# DRV10987.net
KiCad netlist of a schematic drawn in EAGLE
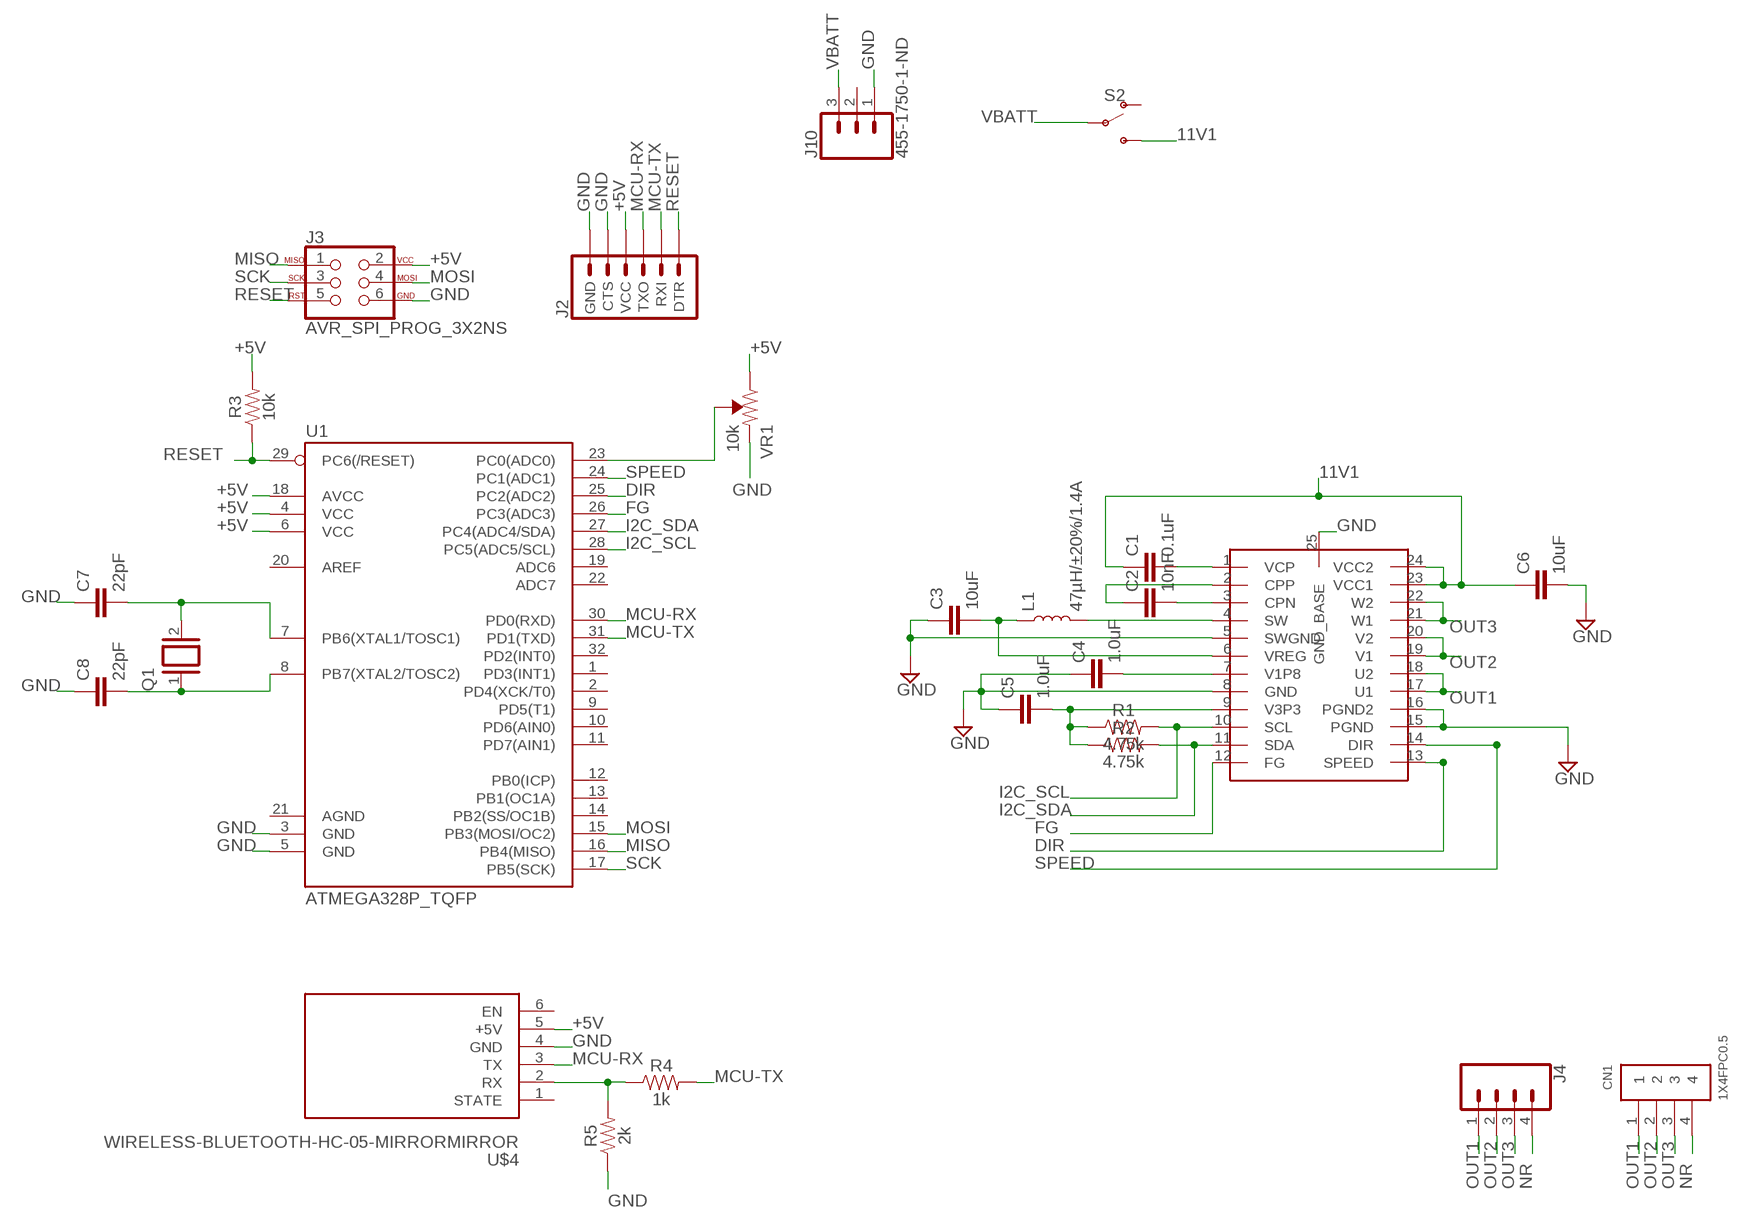
[diagram p0: schematic, sheet 1]

(export (version "E")
  (design (tool "Eeschema 10.0.6"))
  (components
    (comp (ref "C1")
      (value "0.1uF")
      (footprint "eagle-import:0805")
      (libsource (lib "eagle-import") (part "1.0UF-0805-25V-10%"))
    )
    (comp (ref "C2")
      (value "10nF")
      (footprint "eagle-import:0805")
      (libsource (lib "eagle-import") (part "1.0UF-0805-25V-10%"))
    )
    (comp (ref "C3")
      (value "10uF")
      (footprint "eagle-import:0805")
      (libsource (lib "eagle-import") (part "1.0UF-0805-25V-10%"))
    )
    (comp (ref "C4")
      (value "1.0uF")
      (footprint "eagle-import:0805")
      (libsource (lib "eagle-import") (part "1.0UF-0805-25V-10%"))
    )
    (comp (ref "C5")
      (value "1.0uF")
      (footprint "eagle-import:0805")
      (libsource (lib "eagle-import") (part "1.0UF-0805-25V-10%"))
    )
    (comp (ref "C6")
      (value "10uF")
      (footprint "eagle-import:0805")
      (libsource (lib "eagle-import") (part "1.0UF-0805-25V-10%"))
    )
    (comp (ref "C7")
      (value "22pF")
      (footprint "eagle-import:1206")
      (libsource (lib "eagle-import") (part "2.2UF-1206-50V-10%"))
    )
    (comp (ref "C8")
      (value "22pF")
      (footprint "eagle-import:1206")
      (libsource (lib "eagle-import") (part "2.2UF-1206-50V-10%"))
    )
    (comp (ref "CN1")
      (value "1X4FPC0.5")
      (footprint "eagle-import:FPC_0.5MM-4")
      (libsource (lib "eagle-import") (part "1X4FPC0.5"))
    )
    (comp (ref "J2")
      (value "6_PIN_SERIAL_TARGET")
      (footprint "eagle-import:1X06")
      (libsource (lib "eagle-import") (part "6_PIN_SERIAL_TARGET"))
    )
    (comp (ref "J3")
      (value "AVR_SPI_PROG_3X2NS")
      (footprint "eagle-import:2X3-NS")
      (libsource (lib "eagle-import") (part "AVR_SPI_PROG_3X2NS"))
    )
    (comp (ref "J4")
      (value "CONN_04")
      (footprint "eagle-import:1X04")
      (libsource (lib "eagle-import") (part "CONN_04"))
    )
    (comp (ref "J10")
      (value "455-1750-1-ND")
      (footprint "eagle-import:1X03")
      (libsource (lib "eagle-import") (part "CONN_03"))
    )
    (comp (ref "L1")
      (value "47µH/±20%/1.4A")
      (footprint "eagle-import:SRN6045")
      (libsource (lib "eagle-import") (part "INDUCTOR-SRN6045-33UH"))
    )
    (comp (ref "Q1")
      (value "XTAL/S")
      (footprint "eagle-import:QS")
      (libsource (lib "eagle-import") (part "XTAL/S"))
    )
    (comp (ref "R1")
      (value "4.75k")
      (footprint "eagle-import:0805")
      (libsource (lib "eagle-import") (part "RESISTOR0805"))
    )
    (comp (ref "R2")
      (value "4.75k")
      (footprint "eagle-import:0805")
      (libsource (lib "eagle-import") (part "RESISTOR0805"))
    )
    (comp (ref "R3")
      (value "10k")
      (footprint "eagle-import:1206")
      (libsource (lib "eagle-import") (part "RESISTOR1206"))
    )
    (comp (ref "R4")
      (value "1k")
      (footprint "eagle-import:AXIAL-0.3")
      (libsource (lib "eagle-import") (part "1KOHM-HORIZ-1/4W-5%"))
    )
    (comp (ref "R5")
      (value "2k")
      (footprint "eagle-import:AXIAL-0.3")
      (libsource (lib "eagle-import") (part "resistors-longpads_RESISTORAXIAL-0.3"))
    )
    (comp (ref "S2")
      (value "SWITCH-SPDT-PTH-11.6X4.0MM")
      (footprint "eagle-import:SWITCH_SPDT_PTH_11.6X4.0MM")
      (libsource (lib "eagle-import") (part "SWITCH-SPDT-PTH-11.6X4.0MM"))
    )
    (comp (ref "U$1")
      (value "DRV10987")
      (footprint "eagle-import:DRV10987")
      (libsource (lib "eagle-import") (part "DRV10987"))
    )
    (comp (ref "U$4")
      (value "WIRELESS-BLUETOOTH-HC-05-MIRRORMIRROR")
      (footprint "eagle-import:WIRELESS-BLUETOOTH-HC-05-MIRROR")
      (libsource (lib "eagle-import") (part "WIRELESS-BLUETOOTH-HC-05-MIRRORMIRROR"))
    )
    (comp (ref "U1")
      (value "ATMEGA328P_TQFP")
      (footprint "eagle-import:TQFP32-08")
      (libsource (lib "eagle-import") (part "ATMEGA328P_TQFP"))
    )
    (comp (ref "VR1")
      (value "10k")
      (footprint "eagle-import:TRIMPOT-PTH-3386U")
      (libsource (lib "eagle-import") (part "TRIMPOT-PTH-10MM-KNOB-1/2W-10%"))
    )
  )
  (nets
    (net (code "1") (name "/+5V") (class "Default")
      (node (ref "J2") (pin "4") (pinfunction "VCC_4") (pintype "passive"))
      (node (ref "J3") (pin "2") (pinfunction "2_2") (pintype "passive"))
      (node (ref "R3") (pin "2") (pinfunction "2_2") (pintype "passive"))
      (node (ref "U$4") (pin "5") (pinfunction "+5V_5") (pintype "power_in"))
      (node (ref "U1") (pin "18") (pinfunction "AVCC_18") (pintype "bidirectional"))
      (node (ref "U1") (pin "4") (pinfunction "VCC_4") (pintype "bidirectional"))
      (node (ref "U1") (pin "6") (pinfunction "VCC_6") (pintype "bidirectional"))
      (node (ref "VR1") (pin "3") (pinfunction "CW_3") (pintype "passive"))
    )
    (net (code "2") (name "/11V1") (class "Default")
      (node (ref "C1") (pin "1") (pinfunction "1_1") (pintype "passive"))
      (node (ref "C6") (pin "1") (pinfunction "1_1") (pintype "passive"))
      (node (ref "S2") (pin "3") (pinfunction "S_3") (pintype "passive"))
      (node (ref "U$1") (pin "23") (pinfunction "VCC1_23") (pintype "bidirectional"))
      (node (ref "U$1") (pin "24") (pinfunction "VCC2_24") (pintype "bidirectional"))
    )
    (net (code "3") (name "/DIR") (class "Default")
      (node (ref "U$1") (pin "13") (pinfunction "SPEED_13") (pintype "bidirectional"))
      (node (ref "U1") (pin "25") (pinfunction "PC2(ADC2)_25") (pintype "bidirectional"))
    )
    (net (code "4") (name "/FG") (class "Default")
      (node (ref "U$1") (pin "12") (pinfunction "FG_12") (pintype "bidirectional"))
      (node (ref "U1") (pin "26") (pinfunction "PC3(ADC3)_26") (pintype "bidirectional"))
    )
    (net (code "5") (name "/I2C_SCL") (class "Default")
      (node (ref "R1") (pin "2") (pinfunction "2_2") (pintype "passive"))
      (node (ref "U$1") (pin "10") (pinfunction "SCL_10") (pintype "bidirectional"))
      (node (ref "U1") (pin "28") (pinfunction "PC5(ADC5/SCL)_28") (pintype "bidirectional"))
    )
    (net (code "6") (name "/I2C_SDA") (class "Default")
      (node (ref "R2") (pin "2") (pinfunction "2_2") (pintype "passive"))
      (node (ref "U$1") (pin "11") (pinfunction "SDA_11") (pintype "bidirectional"))
      (node (ref "U1") (pin "27") (pinfunction "PC4(ADC4/SDA)_27") (pintype "bidirectional"))
    )
    (net (code "7") (name "/MCU-RX") (class "Default")
      (node (ref "J2") (pin "3") (pinfunction "TXO_3") (pintype "passive"))
      (node (ref "U$4") (pin "3") (pinfunction "TX_3") (pintype "bidirectional"))
      (node (ref "U1") (pin "30") (pinfunction "PD0(RXD)_30") (pintype "bidirectional"))
    )
    (net (code "8") (name "/MCU-TX") (class "Default")
      (node (ref "J2") (pin "2") (pinfunction "RXI_2") (pintype "passive"))
      (node (ref "R4") (pin "P$2") (pinfunction "2_P$2") (pintype "passive"))
      (node (ref "U1") (pin "31") (pinfunction "PD1(TXD)_31") (pintype "bidirectional"))
    )
    (net (code "9") (name "/MISO") (class "Default")
      (node (ref "J3") (pin "1") (pinfunction "1_1") (pintype "passive"))
      (node (ref "U1") (pin "16") (pinfunction "PB4(MISO)_16") (pintype "bidirectional"))
    )
    (net (code "10") (name "/MOSI") (class "Default")
      (node (ref "J3") (pin "4") (pinfunction "4_4") (pintype "passive"))
      (node (ref "U1") (pin "15") (pinfunction "PB3(MOSI/OC2)_15") (pintype "bidirectional"))
    )
    (net (code "11") (name "/NR") (class "Default")
      (node (ref "CN1") (pin "4") (pinfunction "4_4") (pintype "bidirectional"))
      (node (ref "J4") (pin "4") (pinfunction "4_4") (pintype "passive"))
    )
    (net (code "12") (name "/OUT1") (class "Default")
      (node (ref "CN1") (pin "1") (pinfunction "1_1") (pintype "bidirectional"))
      (node (ref "J4") (pin "1") (pinfunction "1_1") (pintype "passive"))
      (node (ref "U$1") (pin "17") (pinfunction "U1_17") (pintype "bidirectional"))
      (node (ref "U$1") (pin "18") (pinfunction "U2_18") (pintype "bidirectional"))
    )
    (net (code "13") (name "/OUT2") (class "Default")
      (node (ref "CN1") (pin "2") (pinfunction "2_2") (pintype "bidirectional"))
      (node (ref "J4") (pin "2") (pinfunction "2_2") (pintype "passive"))
      (node (ref "U$1") (pin "19") (pinfunction "V1_19") (pintype "bidirectional"))
      (node (ref "U$1") (pin "20") (pinfunction "V2_20") (pintype "bidirectional"))
    )
    (net (code "14") (name "/OUT3") (class "Default")
      (node (ref "CN1") (pin "3") (pinfunction "3_3") (pintype "bidirectional"))
      (node (ref "J4") (pin "3") (pinfunction "3_3") (pintype "passive"))
      (node (ref "U$1") (pin "21") (pinfunction "W1_21") (pintype "bidirectional"))
      (node (ref "U$1") (pin "22") (pinfunction "W2_22") (pintype "bidirectional"))
    )
    (net (code "15") (name "/RESET") (class "Default")
      (node (ref "J2") (pin "1") (pinfunction "DTR_1") (pintype "passive"))
      (node (ref "J3") (pin "5") (pinfunction "5_5") (pintype "passive"))
      (node (ref "R3") (pin "1") (pinfunction "1_1") (pintype "passive"))
      (node (ref "U1") (pin "29") (pinfunction "PC6(/RESET)_29") (pintype "bidirectional"))
    )
    (net (code "16") (name "/SCK") (class "Default")
      (node (ref "J3") (pin "3") (pinfunction "3_3") (pintype "passive"))
      (node (ref "U1") (pin "17") (pinfunction "PB5(SCK)_17") (pintype "bidirectional"))
    )
    (net (code "17") (name "/SPEED") (class "Default")
      (node (ref "U$1") (pin "14") (pinfunction "DIR_14") (pintype "bidirectional"))
      (node (ref "U1") (pin "24") (pinfunction "PC1(ADC1)_24") (pintype "bidirectional"))
    )
    (net (code "18") (name "/VBATT") (class "Default")
      (node (ref "J10") (pin "3") (pinfunction "3_3") (pintype "passive"))
      (node (ref "S2") (pin "2") (pinfunction "P_2") (pintype "passive"))
    )
    (net (code "19") (name "GND") (class "Default")
      (node (ref "C3") (pin "1") (pinfunction "1_1") (pintype "passive"))
      (node (ref "C4") (pin "1") (pinfunction "1_1") (pintype "passive"))
      (node (ref "C5") (pin "1") (pinfunction "1_1") (pintype "passive"))
      (node (ref "C6") (pin "2") (pinfunction "2_2") (pintype "passive"))
      (node (ref "C7") (pin "1") (pinfunction "1_1") (pintype "passive"))
      (node (ref "C8") (pin "1") (pinfunction "1_1") (pintype "passive"))
      (node (ref "J10") (pin "1") (pinfunction "1_1") (pintype "passive"))
      (node (ref "J2") (pin "5") (pinfunction "CTS_5") (pintype "passive"))
      (node (ref "J2") (pin "6") (pinfunction "GND_6") (pintype "passive"))
      (node (ref "J3") (pin "6") (pinfunction "6_6") (pintype "passive"))
      (node (ref "R5") (pin "P$1") (pinfunction "1_P$1") (pintype "passive"))
      (node (ref "U$1") (pin "15") (pinfunction "PGND_15") (pintype "bidirectional"))
      (node (ref "U$1") (pin "16") (pinfunction "PGND2_16") (pintype "bidirectional"))
      (node (ref "U$1") (pin "25") (pinfunction "GND_BASE_25") (pintype "bidirectional"))
      (node (ref "U$1") (pin "5") (pinfunction "SWGND_5") (pintype "bidirectional"))
      (node (ref "U$1") (pin "8") (pinfunction "GND_8") (pintype "bidirectional"))
      (node (ref "U$4") (pin "4") (pinfunction "GND_4") (pintype "power_in"))
      (node (ref "U1") (pin "3") (pinfunction "GND_3") (pintype "bidirectional"))
      (node (ref "U1") (pin "5") (pinfunction "GND_5") (pintype "bidirectional"))
      (node (ref "VR1") (pin "1") (pinfunction "CCW_1") (pintype "passive"))
    )
    (net (code "20") (name "Net-(R4-1)") (class "Default")
      (node (ref "R4") (pin "P$1") (pinfunction "1_P$1") (pintype "passive"))
      (node (ref "R5") (pin "P$2") (pinfunction "2_P$2") (pintype "passive"))
      (node (ref "U$4") (pin "2") (pinfunction "RX_2") (pintype "bidirectional"))
    )
    (net (code "21") (name "Net-(U$1-CPN)") (class "Default")
      (node (ref "C2") (pin "2") (pinfunction "2_2") (pintype "passive"))
      (node (ref "U$1") (pin "3") (pinfunction "CPN_3") (pintype "bidirectional"))
    )
    (net (code "22") (name "Net-(U$1-CPP)") (class "Default")
      (node (ref "C2") (pin "1") (pinfunction "1_1") (pintype "passive"))
      (node (ref "U$1") (pin "2") (pinfunction "CPP_2") (pintype "bidirectional"))
    )
    (net (code "23") (name "Net-(U$1-SW)") (class "Default")
      (node (ref "L1") (pin "2") (pinfunction "2_2") (pintype "passive"))
      (node (ref "U$1") (pin "4") (pinfunction "SW_4") (pintype "bidirectional"))
    )
    (net (code "24") (name "Net-(U$1-V1P8)") (class "Default")
      (node (ref "C4") (pin "2") (pinfunction "2_2") (pintype "passive"))
      (node (ref "U$1") (pin "7") (pinfunction "V1P8_7") (pintype "bidirectional"))
    )
    (net (code "25") (name "Net-(U$1-V3P3)") (class "Default")
      (node (ref "C5") (pin "2") (pinfunction "2_2") (pintype "passive"))
      (node (ref "R1") (pin "1") (pinfunction "1_1") (pintype "passive"))
      (node (ref "R2") (pin "1") (pinfunction "1_1") (pintype "passive"))
      (node (ref "U$1") (pin "9") (pinfunction "V3P3_9") (pintype "bidirectional"))
    )
    (net (code "26") (name "Net-(U$1-VCP)") (class "Default")
      (node (ref "C1") (pin "2") (pinfunction "2_2") (pintype "passive"))
      (node (ref "U$1") (pin "1") (pinfunction "VCP_1") (pintype "bidirectional"))
    )
    (net (code "27") (name "Net-(U$1-VREG)") (class "Default")
      (node (ref "C3") (pin "2") (pinfunction "2_2") (pintype "passive"))
      (node (ref "L1") (pin "1") (pinfunction "1_1") (pintype "passive"))
      (node (ref "U$1") (pin "6") (pinfunction "VREG_6") (pintype "bidirectional"))
    )
    (net (code "28") (name "Net-(U1-PB6(XTAL1{slash}TOSC1))") (class "Default")
      (node (ref "C7") (pin "2") (pinfunction "2_2") (pintype "passive"))
      (node (ref "Q1") (pin "2") (pinfunction "2_2") (pintype "passive"))
      (node (ref "U1") (pin "7") (pinfunction "PB6(XTAL1/TOSC1)_7") (pintype "bidirectional"))
    )
    (net (code "29") (name "Net-(U1-PB7(XTAL2{slash}TOSC2))") (class "Default")
      (node (ref "C8") (pin "2") (pinfunction "2_2") (pintype "passive"))
      (node (ref "Q1") (pin "1") (pinfunction "1_1") (pintype "passive"))
      (node (ref "U1") (pin "8") (pinfunction "PB7(XTAL2/TOSC2)_8") (pintype "bidirectional"))
    )
    (net (code "30") (name "Net-(U1-PC0(ADC0))") (class "Default")
      (node (ref "U1") (pin "23") (pinfunction "PC0(ADC0)_23") (pintype "bidirectional"))
      (node (ref "VR1") (pin "2") (pinfunction "WIPER_2") (pintype "passive"))
    )
    (net (code "31") (name "unconnected-(J10-Pad2)") (class "Default")
      (node (ref "J10") (pin "2") (pinfunction "2_2") (pintype "passive"))
    )
    (net (code "32") (name "unconnected-(S2-O-Pad1)") (class "Default")
      (node (ref "S2") (pin "1") (pinfunction "O_1") (pintype "passive"))
    )
    (net (code "33") (name "unconnected-(U$4-EN-Pad6)") (class "Default")
      (node (ref "U$4") (pin "6") (pinfunction "EN_6") (pintype "bidirectional"))
    )
    (net (code "34") (name "unconnected-(U$4-STATE-Pad1)") (class "Default")
      (node (ref "U$4") (pin "1") (pinfunction "STATE_1") (pintype "bidirectional"))
    )
    (net (code "35") (name "unconnected-(U1-ADC6-Pad19)") (class "Default")
      (node (ref "U1") (pin "19") (pinfunction "ADC6_19") (pintype "bidirectional"))
    )
    (net (code "36") (name "unconnected-(U1-ADC7-Pad22)") (class "Default")
      (node (ref "U1") (pin "22") (pinfunction "ADC7_22") (pintype "bidirectional"))
    )
    (net (code "37") (name "unconnected-(U1-AGND-Pad21)") (class "Default")
      (node (ref "U1") (pin "21") (pinfunction "AGND_21") (pintype "bidirectional"))
    )
    (net (code "38") (name "unconnected-(U1-AREF-Pad20)") (class "Default")
      (node (ref "U1") (pin "20") (pinfunction "AREF_20") (pintype "bidirectional"))
    )
    (net (code "39") (name "unconnected-(U1-PB0(ICP)-Pad12)") (class "Default")
      (node (ref "U1") (pin "12") (pinfunction "PB0(ICP)_12") (pintype "bidirectional"))
    )
    (net (code "40") (name "unconnected-(U1-PB1(OC1A)-Pad13)") (class "Default")
      (node (ref "U1") (pin "13") (pinfunction "PB1(OC1A)_13") (pintype "bidirectional"))
    )
    (net (code "41") (name "unconnected-(U1-PB2(SS{slash}OC1B)-Pad14)") (class "Default")
      (node (ref "U1") (pin "14") (pinfunction "PB2(SS/OC1B)_14") (pintype "bidirectional"))
    )
    (net (code "42") (name "unconnected-(U1-PD2(INT0)-Pad32)") (class "Default")
      (node (ref "U1") (pin "32") (pinfunction "PD2(INT0)_32") (pintype "bidirectional"))
    )
    (net (code "43") (name "unconnected-(U1-PD3(INT1)-Pad1)") (class "Default")
      (node (ref "U1") (pin "1") (pinfunction "PD3(INT1)_1") (pintype "bidirectional"))
    )
    (net (code "44") (name "unconnected-(U1-PD4(XCK{slash}T0)-Pad2)") (class "Default")
      (node (ref "U1") (pin "2") (pinfunction "PD4(XCK/T0)_2") (pintype "bidirectional"))
    )
    (net (code "45") (name "unconnected-(U1-PD5(T1)-Pad9)") (class "Default")
      (node (ref "U1") (pin "9") (pinfunction "PD5(T1)_9") (pintype "bidirectional"))
    )
    (net (code "46") (name "unconnected-(U1-PD6(AIN0)-Pad10)") (class "Default")
      (node (ref "U1") (pin "10") (pinfunction "PD6(AIN0)_10") (pintype "bidirectional"))
    )
    (net (code "47") (name "unconnected-(U1-PD7(AIN1)-Pad11)") (class "Default")
      (node (ref "U1") (pin "11") (pinfunction "PD7(AIN1)_11") (pintype "bidirectional"))
    )
  )
)
